# WemosD1MiniShield.net
KiCad netlist of a schematic drawn in EAGLE
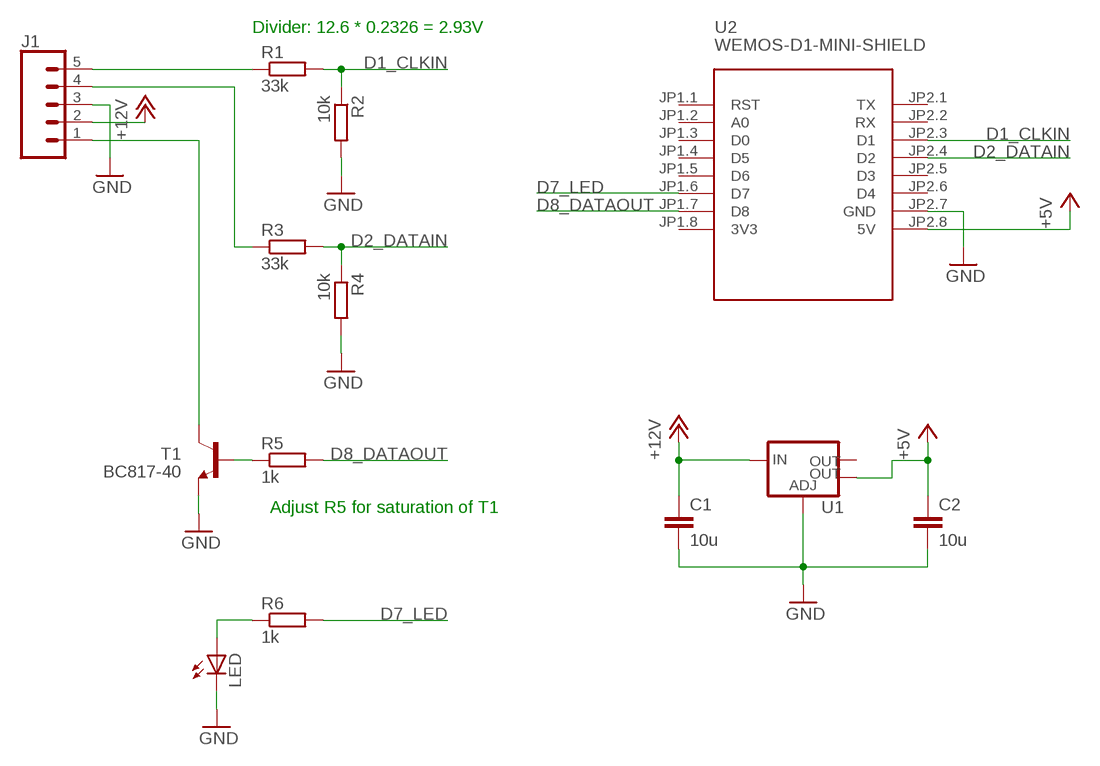
[diagram p0: schematic, sheet 1]

(export (version "E")
  (design (tool "Eeschema 10.0.6"))
  (components
    (comp (ref "C1")
      (value "10u")
      (footprint "eagle-import:C0805")
      (libsource (lib "eagle-import") (part "C-EUC0805"))
    )
    (comp (ref "C2")
      (value "10u")
      (footprint "eagle-import:C0805")
      (libsource (lib "eagle-import") (part "C-EUC0805"))
    )
    (comp (ref "J1")
      (value "CONN_05LOCK")
      (footprint "eagle-import:1X05_LOCK")
      (libsource (lib "eagle-import") (part "CONN_05LOCK"))
    )
    (comp (ref "LED")
      (value "LED1206")
      (footprint "eagle-import:LED-1206")
      (libsource (lib "eagle-import") (part "LED1206"))
    )
    (comp (ref "R1")
      (value "33k")
      (footprint "eagle-import:R0805")
      (libsource (lib "eagle-import") (part "R-EU_R0805"))
    )
    (comp (ref "R2")
      (value "10k")
      (footprint "eagle-import:R0805")
      (libsource (lib "eagle-import") (part "R-EU_R0805"))
    )
    (comp (ref "R3")
      (value "33k")
      (footprint "eagle-import:R0805")
      (libsource (lib "eagle-import") (part "R-EU_R0805"))
    )
    (comp (ref "R4")
      (value "10k")
      (footprint "eagle-import:R0805")
      (libsource (lib "eagle-import") (part "R-EU_R0805"))
    )
    (comp (ref "R5")
      (value "1k")
      (footprint "eagle-import:R0805")
      (libsource (lib "eagle-import") (part "R-EU_R0805"))
    )
    (comp (ref "R6")
      (value "1k")
      (footprint "eagle-import:R0805")
      (libsource (lib "eagle-import") (part "R-EU_R0805"))
    )
    (comp (ref "T1")
      (value "BC817-40")
      (footprint "eagle-import:SOT23-BEC")
      (libsource (lib "eagle-import") (part "-NPN-SOT23-BECBC817-40"))
    )
    (comp (ref "U1")
      (value "V_REG_LM1117SOT223")
      (footprint "eagle-import:SOT223")
      (libsource (lib "eagle-import") (part "V_REG_LM1117SOT223"))
    )
    (comp (ref "U2")
      (value "WEMOS-D1-MINI-SHIELD")
      (footprint "eagle-import:WEMOS-D1-MINI-SHIELD")
      (libsource (lib "eagle-import") (part "WEMOS-D1-MINI-SHIELD"))
    )
  )
  (nets
    (net (code "1") (name "+5V") (class "Default")
      (node (ref "C2") (pin "1") (pinfunction "1_1") (pintype "passive"))
      (node (ref "U1") (pin "4") (pinfunction "OUT_4") (pintype "output"))
      (node (ref "U2") (pin "JP2.8") (pinfunction "5V_JP2.8") (pintype "power_in"))
    )
    (net (code "2") (name "+12V") (class "Default")
      (node (ref "C1") (pin "1") (pinfunction "1_1") (pintype "passive"))
      (node (ref "J1") (pin "2") (pinfunction "2_2") (pintype "passive"))
      (node (ref "U1") (pin "3") (pinfunction "IN_3") (pintype "input"))
    )
    (net (code "3") (name "/3V3") (class "Default")
      (node (ref "U2") (pin "JP1.8") (pinfunction "3V3_JP1.8") (pintype "power_in"))
    )
    (net (code "4") (name "/D1_CLKIN") (class "Default")
      (node (ref "R1") (pin "2") (pinfunction "2_2") (pintype "passive"))
      (node (ref "R2") (pin "1") (pinfunction "1_1") (pintype "passive"))
      (node (ref "U2") (pin "JP2.3") (pinfunction "D1_JP2.3") (pintype "bidirectional"))
    )
    (net (code "5") (name "/D2_DATAIN") (class "Default")
      (node (ref "R3") (pin "2") (pinfunction "2_2") (pintype "passive"))
      (node (ref "R4") (pin "1") (pinfunction "1_1") (pintype "passive"))
      (node (ref "U2") (pin "JP2.4") (pinfunction "D2_JP2.4") (pintype "bidirectional"))
    )
    (net (code "6") (name "/D7_LED") (class "Default")
      (node (ref "R6") (pin "2") (pinfunction "2_2") (pintype "passive"))
      (node (ref "U2") (pin "JP1.6") (pinfunction "D7_JP1.6") (pintype "bidirectional"))
    )
    (net (code "7") (name "/D8_DATAOUT") (class "Default")
      (node (ref "R5") (pin "2") (pinfunction "2_2") (pintype "passive"))
      (node (ref "U2") (pin "JP1.7") (pinfunction "D8_JP1.7") (pintype "bidirectional"))
    )
    (net (code "8") (name "GND") (class "Default")
      (node (ref "C1") (pin "2") (pinfunction "2_2") (pintype "passive"))
      (node (ref "C2") (pin "2") (pinfunction "2_2") (pintype "passive"))
      (node (ref "J1") (pin "3") (pinfunction "3_3") (pintype "passive"))
      (node (ref "LED") (pin "C") (pinfunction "C_C") (pintype "passive"))
      (node (ref "R2") (pin "2") (pinfunction "2_2") (pintype "passive"))
      (node (ref "R4") (pin "2") (pinfunction "2_2") (pintype "passive"))
      (node (ref "T1") (pin "E") (pinfunction "E_E") (pintype "passive"))
      (node (ref "U1") (pin "1") (pinfunction "ADJ_1") (pintype "input"))
      (node (ref "U2") (pin "JP2.7") (pinfunction "GND_JP2.7") (pintype "power_in"))
    )
    (net (code "9") (name "Net-(J1-Pad1)") (class "Default")
      (node (ref "J1") (pin "1") (pinfunction "1_1") (pintype "passive"))
      (node (ref "T1") (pin "C") (pinfunction "C_C") (pintype "passive"))
    )
    (net (code "10") (name "Net-(J1-Pad4)") (class "Default")
      (node (ref "J1") (pin "4") (pinfunction "4_4") (pintype "passive"))
      (node (ref "R3") (pin "1") (pinfunction "1_1") (pintype "passive"))
    )
    (net (code "11") (name "Net-(J1-Pad5)") (class "Default")
      (node (ref "J1") (pin "5") (pinfunction "5_5") (pintype "passive"))
      (node (ref "R1") (pin "1") (pinfunction "1_1") (pintype "passive"))
    )
    (net (code "12") (name "Net-(LED-PadA)") (class "Default")
      (node (ref "LED") (pin "A") (pinfunction "A_A") (pintype "passive"))
      (node (ref "R6") (pin "1") (pinfunction "1_1") (pintype "passive"))
    )
    (net (code "13") (name "Net-(R5-Pad1)") (class "Default")
      (node (ref "R5") (pin "1") (pinfunction "1_1") (pintype "passive"))
      (node (ref "T1") (pin "B") (pinfunction "B_B") (pintype "passive"))
    )
    (net (code "14") (name "unconnected-(U1-OUT-Pad2)") (class "Default")
      (node (ref "U1") (pin "2") (pinfunction "OUT_2") (pintype "output"))
    )
    (net (code "15") (name "unconnected-(U2-A0-PadJP1.2)") (class "Default")
      (node (ref "U2") (pin "JP1.2") (pinfunction "A0_JP1.2") (pintype "bidirectional"))
    )
    (net (code "16") (name "unconnected-(U2-D0-PadJP1.3)") (class "Default")
      (node (ref "U2") (pin "JP1.3") (pinfunction "D0_JP1.3") (pintype "bidirectional"))
    )
    (net (code "17") (name "unconnected-(U2-D3-PadJP2.5)") (class "Default")
      (node (ref "U2") (pin "JP2.5") (pinfunction "D3_JP2.5") (pintype "bidirectional"))
    )
    (net (code "18") (name "unconnected-(U2-D4-PadJP2.6)") (class "Default")
      (node (ref "U2") (pin "JP2.6") (pinfunction "D4_JP2.6") (pintype "bidirectional"))
    )
    (net (code "19") (name "unconnected-(U2-D5-PadJP1.4)") (class "Default")
      (node (ref "U2") (pin "JP1.4") (pinfunction "D5_JP1.4") (pintype "bidirectional"))
    )
    (net (code "20") (name "unconnected-(U2-D6-PadJP1.5)") (class "Default")
      (node (ref "U2") (pin "JP1.5") (pinfunction "D6_JP1.5") (pintype "bidirectional"))
    )
    (net (code "21") (name "unconnected-(U2-RST-PadJP1.1)") (class "Default")
      (node (ref "U2") (pin "JP1.1") (pinfunction "RST_JP1.1") (pintype "bidirectional"))
    )
    (net (code "22") (name "unconnected-(U2-RX-PadJP2.2)") (class "Default")
      (node (ref "U2") (pin "JP2.2") (pinfunction "RX_JP2.2") (pintype "bidirectional"))
    )
    (net (code "23") (name "unconnected-(U2-TX-PadJP2.1)") (class "Default")
      (node (ref "U2") (pin "JP2.1") (pinfunction "TX_JP2.1") (pintype "bidirectional"))
    )
  )
)
